# MSP_Power_Program.net
KiCad netlist of a schematic drawn in Altium Designer
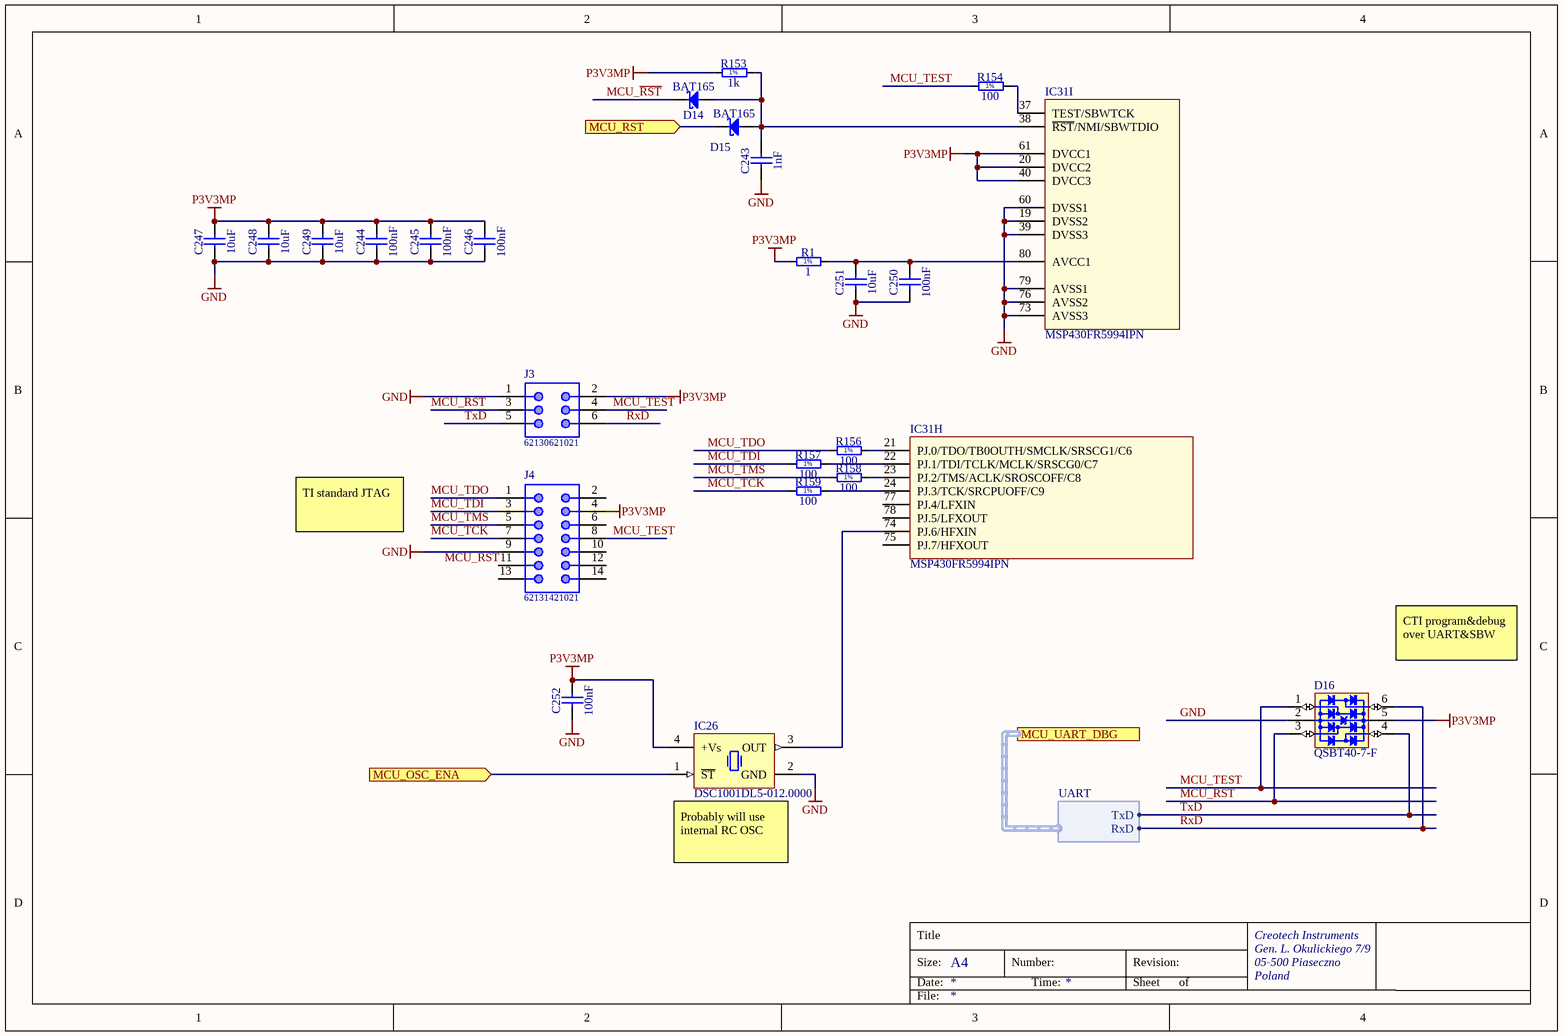
[diagram p0: MSP_Power_Program.SchDoc]

(export (version "E")
  (design (tool "Eeschema 10.0.6"))
  (components
    (comp (ref "C243")
      (value "1nF")
      (footprint "CAPC1005X55N")
      (description "Non-polarised capacitor")
      (fields
        (field (name "PART NUMBER") "CC0402_1NF_50V_10%_X7R")
        (field (name "VOLTAGE") "50V")
        (field (name "AUTHOR") "CERN DEM JLC")
      )
      (libsource (lib "Capacitors") (part "Capacitor - non polarized"))
    )
    (comp (ref "C244")
      (value "100nF")
      (footprint "CAPC1005X55N")
      (description "Non-polarised capacitor")
      (fields
        (field (name "PART NUMBER") "CC0402_100NF_25V_10%_X7R_YUDEN_TMK105B7104KVHF")
        (field (name "VOLTAGE") "25V")
        (field (name "AUTHOR") "CERN DEM JLC")
      )
      (libsource (lib "Capacitors") (part "Capacitor - non polarized"))
    )
    (comp (ref "C245")
      (value "100nF")
      (footprint "CAPC1005X55N")
      (description "Non-polarised capacitor")
      (fields
        (field (name "PART NUMBER") "CC0402_100NF_25V_10%_X7R_YUDEN_TMK105B7104KVHF")
        (field (name "VOLTAGE") "25V")
        (field (name "AUTHOR") "CERN DEM JLC")
      )
      (libsource (lib "Capacitors") (part "Capacitor - non polarized"))
    )
    (comp (ref "C246")
      (value "100nF")
      (footprint "CAPC1005X55N")
      (description "Non-polarised capacitor")
      (fields
        (field (name "PART NUMBER") "CC0402_100NF_25V_10%_X7R_YUDEN_TMK105B7104KVHF")
        (field (name "VOLTAGE") "25V")
        (field (name "AUTHOR") "CERN DEM JLC")
      )
      (libsource (lib "Capacitors") (part "Capacitor - non polarized"))
    )
    (comp (ref "C247")
      (value "10uF")
      (footprint "CAPC1608X80N")
      (description "Non-polarised capacitor")
      (fields
        (field (name "PART NUMBER") "CC0603_10UF_16V_20%_X5R")
        (field (name "VOLTAGE") "16V")
        (field (name "AUTHOR") "CERN DEM MR")
      )
      (libsource (lib "Capacitors") (part "Capacitor - non polarized"))
    )
    (comp (ref "C248")
      (value "10uF")
      (footprint "CAPC1608X80N")
      (description "Non-polarised capacitor")
      (fields
        (field (name "PART NUMBER") "CC0603_10UF_16V_20%_X5R")
        (field (name "VOLTAGE") "16V")
        (field (name "AUTHOR") "CERN DEM MR")
      )
      (libsource (lib "Capacitors") (part "Capacitor - non polarized"))
    )
    (comp (ref "C249")
      (value "10uF")
      (footprint "CAPC1608X80N")
      (description "Non-polarised capacitor")
      (fields
        (field (name "PART NUMBER") "CC0603_10UF_16V_20%_X5R")
        (field (name "VOLTAGE") "16V")
        (field (name "AUTHOR") "CERN DEM MR")
      )
      (libsource (lib "Capacitors") (part "Capacitor - non polarized"))
    )
    (comp (ref "C250")
      (value "100nF")
      (footprint "CAPC1005X55N")
      (description "Non-polarised capacitor")
      (fields
        (field (name "PART NUMBER") "CC0402_100NF_25V_10%_X7R_YUDEN_TMK105B7104KVHF")
        (field (name "VOLTAGE") "25V")
        (field (name "AUTHOR") "CERN DEM JLC")
      )
      (libsource (lib "Capacitors") (part "Capacitor - non polarized"))
    )
    (comp (ref "C251")
      (value "10uF")
      (footprint "CAPC1608X80N")
      (description "Non-polarised capacitor")
      (fields
        (field (name "PART NUMBER") "CC0603_10UF_16V_20%_X5R")
        (field (name "VOLTAGE") "16V")
        (field (name "AUTHOR") "CERN DEM MR")
      )
      (libsource (lib "Capacitors") (part "Capacitor - non polarized"))
    )
    (comp (ref "C252")
      (value "100nF")
      (footprint "CAPC1005X55N")
      (description "Non-polarised capacitor")
      (fields
        (field (name "PART NUMBER") "CC0402_100NF_25V_10%_X7R_YUDEN_TMK105B7104KVHF")
        (field (name "VOLTAGE") "25V")
        (field (name "AUTHOR") "CERN DEM JLC")
      )
      (libsource (lib "Capacitors") (part "Capacitor - non polarized"))
    )
    (comp (ref "D14")
      (value "BAT165")
      (footprint "SOD2512X110N")
      (description "Schottky Diode")
      (fields
        (field (name "VOLTAGE") "40V")
        (field (name "POWER") "750mA")
        (field (name "AUTHOR") "CERN DEM JLC")
      )
      (libsource (lib "ICs And Semiconductors") (part "Diode Schottky"))
    )
    (comp (ref "D15")
      (value "BAT165")
      (footprint "SOD2512X110N")
      (description "Schottky Diode")
      (fields
        (field (name "VOLTAGE") "40V")
        (field (name "POWER") "750mA")
        (field (name "AUTHOR") "CERN DEM JLC")
      )
      (libsource (lib "ICs And Semiconductors") (part "Diode Schottky"))
    )
    (comp (ref "D16")
      (value "QSBT40-7-F")
      (footprint "SOT65P210X110-6N")
      (libsource (lib "LIBRARY_SCH") (part "D_TVS_QSBT40-7-F"))
    )
    (comp (ref "IC26")
      (value "DSC1001DL5-012.0000")
      (footprint "OSC_MICREL_2520")
      (description "MEMS Oscillator 12MHz")
      (fields (field (name "MANUFACTURER") "Micrel"))
      (libsource (lib "LIBRARY_SCH") (part "OSC_DSC1001DL5-012.0000"))
    )
    (comp (ref "IC31")
      (value "MSP430FR5994IPN")
      (footprint "PQFP50P1400X1400-80N")
      (fields (field (name "MANUFACTURER") "TI"))
      (libsource (lib "LIBRARY_SCH") (part "UPC_MSP430FR5994IPN"))
    )
    (comp (ref "J3")
      (value "62130621021")
      (footprint "62130621021")
      (description "SMT Vertical Pin Header WR-PHD, Pitch 1.27 mm, Dual Row, 6 pins")
      (fields (field (name "PUBLISHER") "Wurth Elektronik"))
      (libsource (lib "ALTIUM-WR-PHD_PIN_HEADER-rev18b") (part "62130621021"))
    )
    (comp (ref "J4")
      (value "62131421021")
      (footprint "62131421021")
      (description "SMT Vertical Pin Header WR-PHD, Pitch 1.27 mm, Dual Row, 14 pins")
      (fields (field (name "PUBLISHER") "Wurth Elektronik"))
      (libsource (lib "ALTIUM-WR-PHD_PIN_HEADER-rev18b") (part "62131421021"))
    )
    (comp (ref "R1")
      (value "1")
      (footprint "RESC1005X40N")
      (description "Resistor - 1%")
      (fields
        (field (name "PART NUMBER") "R0402_1R_1%_0.0625W_200PPM")
        (field (name "POWER") "0.0625W")
        (field (name "AUTHOR") "CERN DEM JLC")
      )
      (libsource (lib "Resistors") (part "Resistor - 1%"))
    )
    (comp (ref "R153")
      (value "1k")
      (footprint "RESC1005X40N")
      (description "Resistor - 1%")
      (fields
        (field (name "PART NUMBER") "R0402_1K_1%_0.0625W_100PPM")
        (field (name "POWER") "0.0625W")
        (field (name "AUTHOR") "CERN DEM JLC")
      )
      (libsource (lib "Resistors") (part "Resistor - 1%"))
    )
    (comp (ref "R154")
      (value "100")
      (footprint "RESC1005X40N")
      (description "Resistor - 1%")
      (fields
        (field (name "PART NUMBER") "R0402_100R_1%_0.0625W_100PPM")
        (field (name "POWER") "0.0625W")
        (field (name "AUTHOR") "CERN DEM JLC")
      )
      (libsource (lib "Resistors") (part "Resistor - 1%"))
    )
    (comp (ref "R156")
      (value "100")
      (footprint "RESC1005X40N")
      (description "Resistor - 1%")
      (fields
        (field (name "PART NUMBER") "R0402_100R_1%_0.0625W_100PPM")
        (field (name "POWER") "0.0625W")
        (field (name "AUTHOR") "CERN DEM JLC")
      )
      (libsource (lib "Resistors") (part "Resistor - 1%"))
    )
    (comp (ref "R157")
      (value "100")
      (footprint "RESC1005X40N")
      (description "Resistor - 1%")
      (fields
        (field (name "PART NUMBER") "R0402_100R_1%_0.0625W_100PPM")
        (field (name "POWER") "0.0625W")
        (field (name "AUTHOR") "CERN DEM JLC")
      )
      (libsource (lib "Resistors") (part "Resistor - 1%"))
    )
    (comp (ref "R158")
      (value "100")
      (footprint "RESC1005X40N")
      (description "Resistor - 1%")
      (fields
        (field (name "PART NUMBER") "R0402_100R_1%_0.0625W_100PPM")
        (field (name "POWER") "0.0625W")
        (field (name "AUTHOR") "CERN DEM JLC")
      )
      (libsource (lib "Resistors") (part "Resistor - 1%"))
    )
    (comp (ref "R159")
      (value "100")
      (footprint "RESC1005X40N")
      (description "Resistor - 1%")
      (fields
        (field (name "PART NUMBER") "R0402_100R_1%_0.0625W_100PPM")
        (field (name "POWER") "0.0625W")
        (field (name "AUTHOR") "CERN DEM JLC")
      )
      (libsource (lib "Resistors") (part "Resistor - 1%"))
    )
  )
  (nets
    (net (code "2") (name "/MCU_OSC_ENA") (class "Default")
      (node (ref "IC26") (pin "1") (pinfunction "ST_1") (pintype "input"))
    )
    (net (code "3") (name "/MCU_RST") (class "Default")
      (node (ref "D15") (pin "1") (pinfunction "C_1") (pintype "passive"))
    )
    (net (code "4") (name "/MCU_TCK") (class "Default")
      (node (ref "J4") (pin "7") (pinfunction "7_7") (pintype "passive"))
      (node (ref "R159") (pin "1") (pinfunction "1_1") (pintype "passive"))
    )
    (net (code "5") (name "/MCU_TDI") (class "Default")
      (node (ref "J4") (pin "3") (pinfunction "3_3") (pintype "passive"))
      (node (ref "R157") (pin "1") (pinfunction "1_1") (pintype "passive"))
    )
    (net (code "6") (name "/MCU_TDO") (class "Default")
      (node (ref "J4") (pin "1") (pinfunction "1_1") (pintype "passive"))
      (node (ref "R156") (pin "1") (pinfunction "1_1") (pintype "passive"))
    )
    (net (code "7") (name "/MCU_TEST") (class "Default")
      (node (ref "D16") (pin "1") (pinfunction "I/O1_1") (pintype "bidirectional"))
      (node (ref "J3") (pin "4") (pinfunction "4_4") (pintype "passive"))
      (node (ref "J4") (pin "8") (pinfunction "8_8") (pintype "passive"))
      (node (ref "R154") (pin "1") (pinfunction "1_1") (pintype "passive"))
    )
    (net (code "8") (name "/MCU_TMS") (class "Default")
      (node (ref "J4") (pin "5") (pinfunction "5_5") (pintype "passive"))
      (node (ref "R158") (pin "1") (pinfunction "1_1") (pintype "passive"))
    )
    (net (code "9") (name "/MCU_~{RST}") (class "Default")
      (node (ref "D14") (pin "1") (pinfunction "C_1") (pintype "passive"))
      (node (ref "D16") (pin "3") (pinfunction "I/O2_3") (pintype "bidirectional"))
      (node (ref "J3") (pin "3") (pinfunction "3_3") (pintype "passive"))
    )
    (net (code "10") (name "/RxD") (class "Default")
      (node (ref "D16") (pin "6") (pinfunction "I/O4_6") (pintype "bidirectional"))
      (node (ref "J3") (pin "6") (pinfunction "6_6") (pintype "passive"))
    )
    (net (code "11") (name "/TxD") (class "Default")
      (node (ref "D16") (pin "4") (pinfunction "I/O3_4") (pintype "bidirectional"))
      (node (ref "J3") (pin "5") (pinfunction "5_5") (pintype "passive"))
    )
    (net (code "13") (name "GND") (class "Default")
      (node (ref "C243") (pin "1") (pinfunction "1_1") (pintype "passive"))
      (node (ref "C244") (pin "1") (pinfunction "1_1") (pintype "passive"))
      (node (ref "C245") (pin "1") (pinfunction "1_1") (pintype "passive"))
      (node (ref "C246") (pin "1") (pinfunction "1_1") (pintype "passive"))
      (node (ref "C247") (pin "1") (pinfunction "1_1") (pintype "passive"))
      (node (ref "C248") (pin "1") (pinfunction "1_1") (pintype "passive"))
      (node (ref "C249") (pin "1") (pinfunction "1_1") (pintype "passive"))
      (node (ref "C250") (pin "1") (pinfunction "1_1") (pintype "passive"))
      (node (ref "C251") (pin "1") (pinfunction "1_1") (pintype "passive"))
      (node (ref "C252") (pin "1") (pinfunction "1_1") (pintype "passive"))
      (node (ref "D16") (pin "2") (pinfunction "GND_2") (pintype "power_in"))
      (node (ref "IC26") (pin "2") (pinfunction "GND_2") (pintype "power_in"))
      (node (ref "IC31") (pin "19") (pinfunction "DVSS2_19") (pintype "passive"))
      (node (ref "IC31") (pin "39") (pinfunction "DVSS3_39") (pintype "passive"))
      (node (ref "IC31") (pin "60") (pinfunction "DVSS1_60") (pintype "passive"))
      (node (ref "IC31") (pin "73") (pinfunction "AVSS3_73") (pintype "passive"))
      (node (ref "IC31") (pin "76") (pinfunction "AVSS2_76") (pintype "passive"))
      (node (ref "IC31") (pin "79") (pinfunction "AVSS1_79") (pintype "passive"))
      (node (ref "J3") (pin "1") (pinfunction "1_1") (pintype "passive"))
      (node (ref "J4") (pin "9") (pinfunction "9_9") (pintype "passive"))
    )
    (net (code "14") (name "Net-(D14-A)") (class "Default")
      (node (ref "C243") (pin "2") (pinfunction "2_2") (pintype "passive"))
      (node (ref "D14") (pin "2") (pinfunction "A_2") (pintype "passive"))
      (node (ref "D15") (pin "2") (pinfunction "A_2") (pintype "passive"))
      (node (ref "IC31") (pin "38") (pinfunction "~{RST}/NMI/SBWTDIO_38") (pintype "passive"))
      (node (ref "R153") (pin "2") (pinfunction "2_2") (pintype "passive"))
    )
    (net (code "15") (name "Net-(IC26-OUT)") (class "Default")
      (node (ref "IC26") (pin "3") (pinfunction "OUT_3") (pintype "output"))
      (node (ref "IC31") (pin "74") (pinfunction "PJ.6/HFXIN_74") (pintype "passive"))
    )
    (net (code "16") (name "Net-(IC31H-PJ.0{slash}TDO{slash}TB0OUTH{slash}SMCLK{slash}SRSCG1{slash}C6)") (class "Default")
      (node (ref "IC31") (pin "21") (pinfunction "PJ.0/TDO/TB0OUTH/SMCLK/SRSCG1/C6_21") (pintype "passive"))
      (node (ref "R156") (pin "2") (pinfunction "2_2") (pintype "passive"))
    )
    (net (code "17") (name "Net-(IC31H-PJ.1{slash}TDI{slash}TCLK{slash}MCLK{slash}SRSCG0{slash}C7)") (class "Default")
      (node (ref "IC31") (pin "22") (pinfunction "PJ.1/TDI/TCLK/MCLK/SRSCG0/C7_22") (pintype "passive"))
      (node (ref "R157") (pin "2") (pinfunction "2_2") (pintype "passive"))
    )
    (net (code "18") (name "Net-(IC31H-PJ.2{slash}TMS{slash}ACLK{slash}SROSCOFF{slash}C8)") (class "Default")
      (node (ref "IC31") (pin "23") (pinfunction "PJ.2/TMS/ACLK/SROSCOFF/C8_23") (pintype "passive"))
      (node (ref "R158") (pin "2") (pinfunction "2_2") (pintype "passive"))
    )
    (net (code "19") (name "Net-(IC31H-PJ.3{slash}TCK{slash}SRCPUOFF{slash}C9)") (class "Default")
      (node (ref "IC31") (pin "24") (pinfunction "PJ.3/TCK/SRCPUOFF/C9_24") (pintype "passive"))
      (node (ref "R159") (pin "2") (pinfunction "2_2") (pintype "passive"))
    )
    (net (code "20") (name "Net-(IC31I-AVCC1)") (class "Default")
      (node (ref "C250") (pin "2") (pinfunction "2_2") (pintype "passive"))
      (node (ref "C251") (pin "2") (pinfunction "2_2") (pintype "passive"))
      (node (ref "IC31") (pin "80") (pinfunction "AVCC1_80") (pintype "passive"))
      (node (ref "R1") (pin "2") (pinfunction "2_2") (pintype "passive"))
    )
    (net (code "21") (name "Net-(IC31I-TEST{slash}SBWTCK)") (class "Default")
      (node (ref "IC31") (pin "37") (pinfunction "TEST/SBWTCK_37") (pintype "passive"))
      (node (ref "R154") (pin "2") (pinfunction "2_2") (pintype "passive"))
    )
    (net (code "22") (name "P3V3MP") (class "Default")
      (node (ref "C244") (pin "2") (pinfunction "2_2") (pintype "passive"))
      (node (ref "C245") (pin "2") (pinfunction "2_2") (pintype "passive"))
      (node (ref "C246") (pin "2") (pinfunction "2_2") (pintype "passive"))
      (node (ref "C247") (pin "2") (pinfunction "2_2") (pintype "passive"))
      (node (ref "C248") (pin "2") (pinfunction "2_2") (pintype "passive"))
      (node (ref "C249") (pin "2") (pinfunction "2_2") (pintype "passive"))
      (node (ref "C252") (pin "2") (pinfunction "2_2") (pintype "passive"))
      (node (ref "D16") (pin "5") (pinfunction "VBUS_5") (pintype "power_in"))
      (node (ref "IC26") (pin "4") (pinfunction "+Vs_4") (pintype "power_in"))
      (node (ref "IC31") (pin "20") (pinfunction "DVCC2_20") (pintype "passive"))
      (node (ref "IC31") (pin "40") (pinfunction "DVCC3_40") (pintype "passive"))
      (node (ref "IC31") (pin "61") (pinfunction "DVCC1_61") (pintype "passive"))
      (node (ref "J3") (pin "2") (pinfunction "2_2") (pintype "passive"))
      (node (ref "J4") (pin "4") (pinfunction "4_4") (pintype "passive"))
      (node (ref "R1") (pin "1") (pinfunction "1_1") (pintype "passive"))
      (node (ref "R153") (pin "1") (pinfunction "1_1") (pintype "passive"))
    )
    (net (code "23") (name "unconnected-(IC31H-PJ.4{slash}LFXIN-Pad77)") (class "Default")
      (node (ref "IC31") (pin "77") (pinfunction "PJ.4/LFXIN_77") (pintype "passive"))
    )
    (net (code "24") (name "unconnected-(IC31H-PJ.5{slash}LFXOUT-Pad78)") (class "Default")
      (node (ref "IC31") (pin "78") (pinfunction "PJ.5/LFXOUT_78") (pintype "passive"))
    )
    (net (code "25") (name "unconnected-(IC31H-PJ.7{slash}HFXOUT-Pad75)") (class "Default")
      (node (ref "IC31") (pin "75") (pinfunction "PJ.7/HFXOUT_75") (pintype "passive"))
    )
    (net (code "26") (name "unconnected-(J4-Pad2)") (class "Default")
      (node (ref "J4") (pin "2") (pinfunction "2_2") (pintype "passive"))
    )
    (net (code "27") (name "unconnected-(J4-Pad6)") (class "Default")
      (node (ref "J4") (pin "6") (pinfunction "6_6") (pintype "passive"))
    )
    (net (code "28") (name "unconnected-(J4-Pad10)") (class "Default")
      (node (ref "J4") (pin "10") (pinfunction "10_10") (pintype "passive"))
    )
    (net (code "29") (name "unconnected-(J4-Pad11)") (class "Default")
      (node (ref "J4") (pin "11") (pinfunction "11_11") (pintype "passive"))
    )
    (net (code "30") (name "unconnected-(J4-Pad12)") (class "Default")
      (node (ref "J4") (pin "12") (pinfunction "12_12") (pintype "passive"))
    )
    (net (code "31") (name "unconnected-(J4-Pad13)") (class "Default")
      (node (ref "J4") (pin "13") (pinfunction "13_13") (pintype "passive"))
    )
    (net (code "32") (name "unconnected-(J4-Pad14)") (class "Default")
      (node (ref "J4") (pin "14") (pinfunction "14_14") (pintype "passive"))
    )
  )
)
